# EDA-Robot_V1_2.net
KiCad netlist of a schematic drawn in EasyEDA Pro
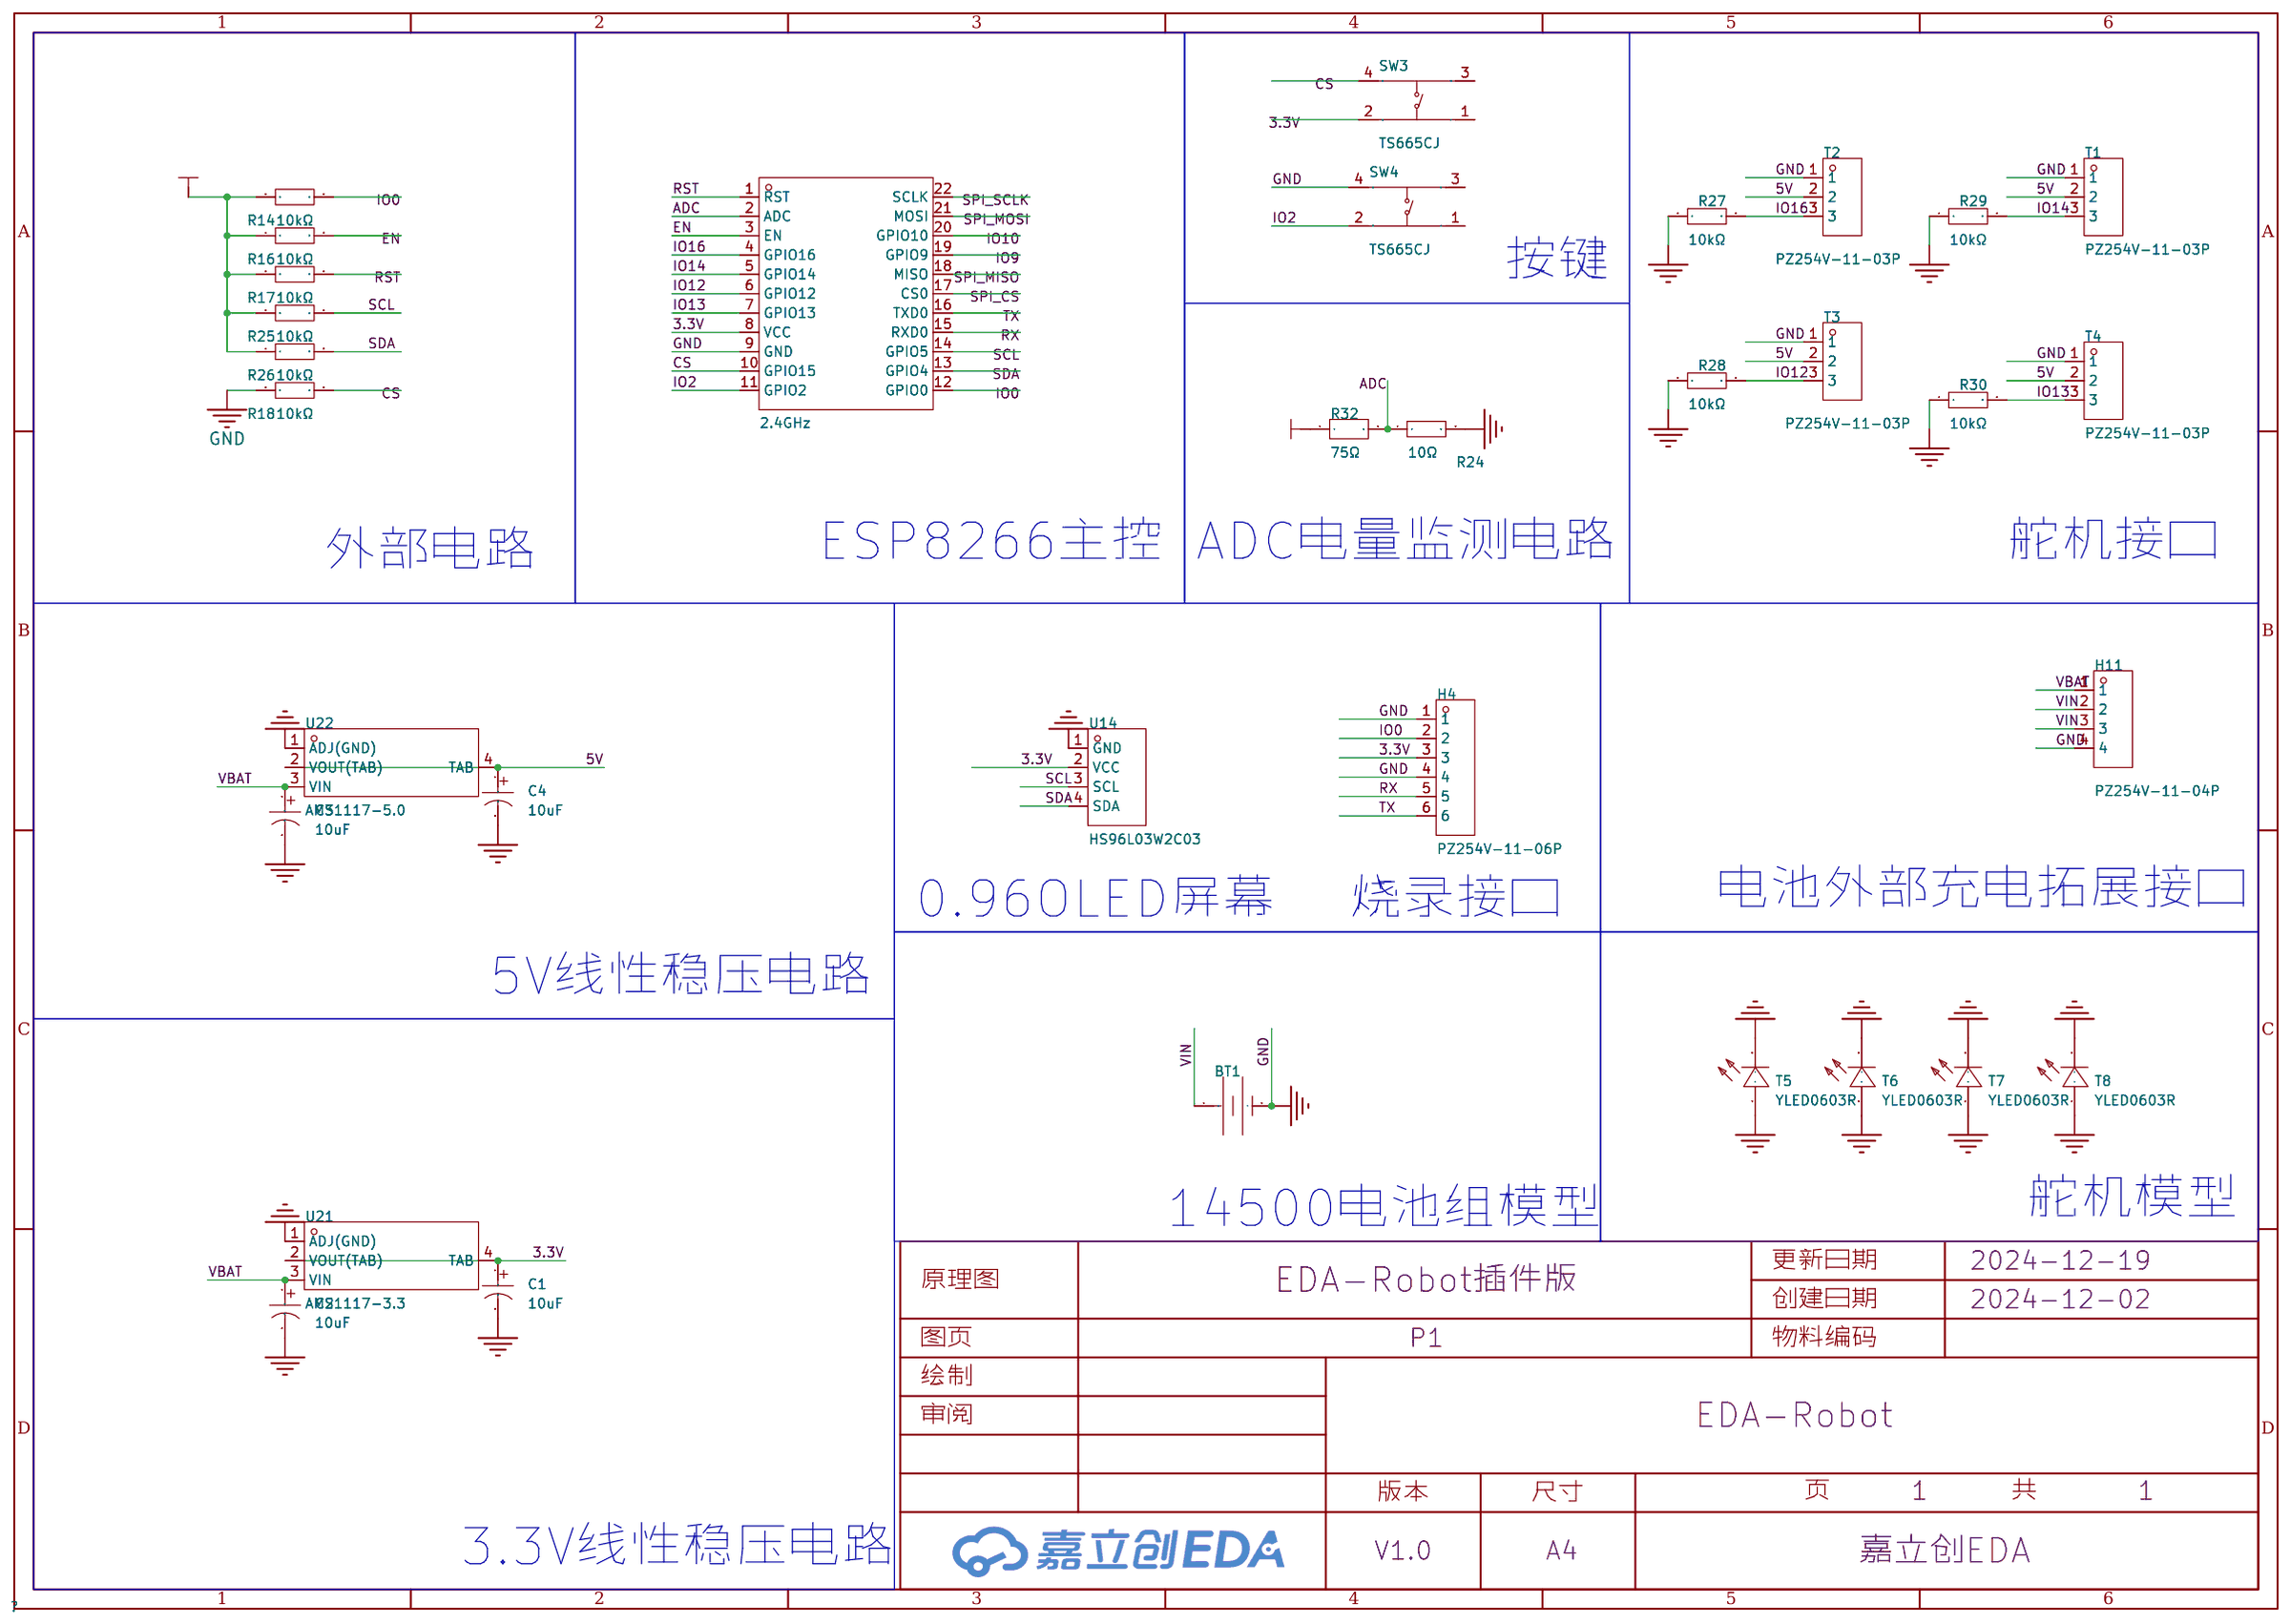
[diagram p0: schematic sheet]

(export (version "E")
  (design (tool "Eeschema 10.0.6"))
  (components
    (comp (ref "BT1")
      (value "BS-12-B3AA003")
      (footprint "easyedapro:BAT-SMD_BS-12-B3AA011")
      (description "连接器类型:电池底座;适用电池规格:CR1220;触头材质:磷青铜;工作温度范围:-25°C~+85°C;")
      (fields (field (name "Manufacturer") "MYOUNG(美阳)"))
      (libsource (lib "easyedapro") (part "BS-12-B3AA003"))
    )
    (comp (ref "C1")
      (value "10uF")
      (footprint "easyedapro:CAP-TH_BD4.0-P1.50-D0.8-FD")
      (description "容值:10uF;精度:±20%;额定电压:25V;纹波电流:29mA@120Hz;等效串联电阻:-;")
      (fields
        (field (name "Manufacturer Part") "KS106M025C07RR0VH2FP0")
        (field (name "Manufacturer") "CX(承兴)")
      )
      (libsource (lib "easyedapro") (part "10uF 25V 4*7"))
    )
    (comp (ref "C2")
      (value "10uF")
      (footprint "easyedapro:CAP-TH_BD4.0-P1.50-D0.8-FD")
      (description "容值:10uF;精度:±20%;额定电压:25V;纹波电流:29mA@120Hz;等效串联电阻:-;")
      (fields
        (field (name "Manufacturer Part") "KS106M025C07RR0VH2FP0")
        (field (name "Manufacturer") "CX(承兴)")
      )
      (libsource (lib "easyedapro") (part "10uF 25V 4*7"))
    )
    (comp (ref "C3")
      (value "10uF")
      (footprint "easyedapro:CAP-TH_BD4.0-P1.50-D0.8-FD")
      (description "容值:10uF;精度:±20%;额定电压:25V;纹波电流:29mA@120Hz;等效串联电阻:-;")
      (fields
        (field (name "Manufacturer Part") "KS106M025C07RR0VH2FP0")
        (field (name "Manufacturer") "CX(承兴)")
      )
      (libsource (lib "easyedapro") (part "10uF 25V 4*7"))
    )
    (comp (ref "C4")
      (value "10uF")
      (footprint "easyedapro:CAP-TH_BD4.0-P1.50-D0.8-FD")
      (description "容值:10uF;精度:±20%;额定电压:25V;纹波电流:29mA@120Hz;等效串联电阻:-;")
      (fields
        (field (name "Manufacturer Part") "KS106M025C07RR0VH2FP0")
        (field (name "Manufacturer") "CX(承兴)")
      )
      (libsource (lib "easyedapro") (part "10uF 25V 4*7"))
    )
    (comp (ref "H4")
      (value "PZ254V-11-06P")
      (footprint "easyedapro:HDR-TH_6P-P2.54-V-M")
      (fields (field (name "Manufacturer") "XFCN(兴飞)"))
      (libsource (lib "easyedapro") (part "PZ254V-11-06P"))
    )
    (comp (ref "H11")
      (value "PZ254V-11-04P")
      (footprint "easyedapro:HDR-TH_4P-P2.54-V-M")
      (fields (field (name "Manufacturer") "XFCN(兴飞)"))
      (libsource (lib "easyedapro") (part "PZ254V-11-04P_C2691448"))
    )
    (comp (ref "R14")
      (value "10kΩ")
      (footprint "easyedapro:R0805")
      (description "电阻类型:厚膜电阻;阻值:10kΩ;精度:±5%;功率:125mW;最大工作电压:150V;温度系数:±100ppm/°C;")
      (fields
        (field (name "Manufacturer Part") "RN1/4W10KFT/BA1")
        (field (name "Manufacturer") "Tyohm(幸亚电阻)")
      )
      (libsource (lib "easyedapro") (part "0805W8J0103T5E"))
    )
    (comp (ref "R16")
      (value "10kΩ")
      (footprint "easyedapro:R0805")
      (description "电阻类型:厚膜电阻;阻值:10kΩ;精度:±5%;功率:125mW;最大工作电压:150V;温度系数:±100ppm/°C;")
      (fields
        (field (name "Manufacturer Part") "RN1/4W10KFT/BA1")
        (field (name "Manufacturer") "Tyohm(幸亚电阻)")
      )
      (libsource (lib "easyedapro") (part "0805W8J0103T5E"))
    )
    (comp (ref "R17")
      (value "10kΩ")
      (footprint "easyedapro:R0805")
      (description "电阻类型:厚膜电阻;阻值:10kΩ;精度:±5%;功率:125mW;最大工作电压:150V;温度系数:±100ppm/°C;")
      (fields
        (field (name "Manufacturer Part") "RN1/4W10KFT/BA1")
        (field (name "Manufacturer") "Tyohm(幸亚电阻)")
      )
      (libsource (lib "easyedapro") (part "0805W8J0103T5E"))
    )
    (comp (ref "R18")
      (value "10kΩ")
      (footprint "easyedapro:R0805")
      (description "电阻类型:厚膜电阻;阻值:10kΩ;精度:±5%;功率:125mW;最大工作电压:150V;温度系数:±100ppm/°C;")
      (fields
        (field (name "Manufacturer Part") "RN1/4W10KFT/BA1")
        (field (name "Manufacturer") "Tyohm(幸亚电阻)")
      )
      (libsource (lib "easyedapro") (part "0805W8J0103T5E"))
    )
    (comp (ref "R24")
      (value "10Ω")
      (footprint "easyedapro:R0805")
      (description "电阻类型:厚膜电阻;阻值:10kΩ;精度:±5%;功率:125mW;最大工作电压:150V;温度系数:±100ppm/°C;")
      (fields (field (name "Manufacturer Part") "MFR-25FTE52-10R") (field (name "Manufacturer") "YAGEO(国巨)"))
      (libsource (lib "easyedapro") (part "0805W8J0103T5E"))
    )
    (comp (ref "R25")
      (value "10kΩ")
      (footprint "easyedapro:R0805")
      (description "电阻类型:厚膜电阻;阻值:10kΩ;精度:±5%;功率:125mW;最大工作电压:150V;温度系数:±100ppm/°C;")
      (fields
        (field (name "Manufacturer Part") "RN1/4W10KFT/BA1")
        (field (name "Manufacturer") "Tyohm(幸亚电阻)")
      )
      (libsource (lib "easyedapro") (part "0805W8J0103T5E"))
    )
    (comp (ref "R26")
      (value "10kΩ")
      (footprint "easyedapro:R0805")
      (description "电阻类型:厚膜电阻;阻值:10kΩ;精度:±5%;功率:125mW;最大工作电压:150V;温度系数:±100ppm/°C;")
      (fields
        (field (name "Manufacturer Part") "RN1/4W10KFT/BA1")
        (field (name "Manufacturer") "Tyohm(幸亚电阻)")
      )
      (libsource (lib "easyedapro") (part "0805W8J0103T5E"))
    )
    (comp (ref "R27")
      (value "10kΩ")
      (footprint "easyedapro:R0805")
      (description "电阻类型:厚膜电阻;阻值:10kΩ;精度:±5%;功率:125mW;最大工作电压:150V;温度系数:±100ppm/°C;")
      (fields
        (field (name "Manufacturer Part") "RN1/4W10KFT/BA1")
        (field (name "Manufacturer") "Tyohm(幸亚电阻)")
      )
      (libsource (lib "easyedapro") (part "0805W8J0103T5E"))
    )
    (comp (ref "R28")
      (value "10kΩ")
      (footprint "easyedapro:R0805")
      (description "电阻类型:厚膜电阻;阻值:10kΩ;精度:±5%;功率:125mW;最大工作电压:150V;温度系数:±100ppm/°C;")
      (fields
        (field (name "Manufacturer Part") "RN1/4W10KFT/BA1")
        (field (name "Manufacturer") "Tyohm(幸亚电阻)")
      )
      (libsource (lib "easyedapro") (part "0805W8J0103T5E"))
    )
    (comp (ref "R29")
      (value "10kΩ")
      (footprint "easyedapro:R0805")
      (description "电阻类型:厚膜电阻;阻值:10kΩ;精度:±5%;功率:125mW;最大工作电压:150V;温度系数:±100ppm/°C;")
      (fields
        (field (name "Manufacturer Part") "RN1/4W10KFT/BA1")
        (field (name "Manufacturer") "Tyohm(幸亚电阻)")
      )
      (libsource (lib "easyedapro") (part "0805W8J0103T5E"))
    )
    (comp (ref "R30")
      (value "10kΩ")
      (footprint "easyedapro:R0805")
      (description "电阻类型:厚膜电阻;阻值:10kΩ;精度:±5%;功率:125mW;最大工作电压:150V;温度系数:±100ppm/°C;")
      (fields
        (field (name "Manufacturer Part") "RN1/4W10KFT/BA1")
        (field (name "Manufacturer") "Tyohm(幸亚电阻)")
      )
      (libsource (lib "easyedapro") (part "0805W8J0103T5E"))
    )
    (comp (ref "R32")
      (value "75Ω")
      (footprint "easyedapro:RES-TH_BD2.4-L6.3-P10.30-D0.6")
      (description "电阻类型:金属膜电阻;阻值:75Ω;精度:±1%;功率:250mW;温度系数:±50ppm/°C;")
      (fields (field (name "Manufacturer Part") "MFR-25FTE52-75R") (field (name "Manufacturer") "YAGEO(国巨)"))
      (libsource (lib "easyedapro") (part "MFR-25FTE52-75R"))
    )
    (comp (ref "SW3")
      (value "TS665CJ")
      (footprint "easyedapro:SW-TH_4P-L6.0-W6.0-P4.50-LS6.5")
      (description "电路结构:单刀单掷;按钮形状:圆形按钮;安装方式:直插;开关长度:6mm;开关宽度:6mm;开关高度:5mm;触点电流:50mA;额定电压(DC):12V;带灯:-;机械寿命:-;")
      (fields (field (name "Manufacturer") "SHOU HAN(首韩)"))
      (libsource (lib "easyedapro") (part "TS665CJ"))
    )
    (comp (ref "SW4")
      (value "TS665CJ")
      (footprint "easyedapro:SW-TH_4P-L6.0-W6.0-P4.50-LS6.5")
      (description "电路结构:单刀单掷;按钮形状:圆形按钮;安装方式:直插;开关长度:6mm;开关宽度:6mm;开关高度:5mm;触点电流:50mA;额定电压(DC):12V;带灯:-;机械寿命:-;")
      (fields (field (name "Manufacturer") "SHOU HAN(首韩)"))
      (libsource (lib "easyedapro") (part "TS665CJ"))
    )
    (comp (ref "T1")
      (value "PZ254V-11-03P")
      (footprint "easyedapro:HDR-TH_3P-P2.54-V-M")
      (fields (field (name "Manufacturer") "XFCN(兴飞)"))
      (libsource (lib "easyedapro") (part "PZ254V-11-03P_C2937625"))
    )
    (comp (ref "T2")
      (value "PZ254V-11-03P")
      (footprint "easyedapro:HDR-TH_3P-P2.54-V-M")
      (fields (field (name "Manufacturer") "XFCN(兴飞)"))
      (libsource (lib "easyedapro") (part "PZ254V-11-03P_C2937625"))
    )
    (comp (ref "T3")
      (value "PZ254V-11-03P")
      (footprint "easyedapro:HDR-TH_3P-P2.54-V-M")
      (fields (field (name "Manufacturer") "XFCN(兴飞)"))
      (libsource (lib "easyedapro") (part "PZ254V-11-03P_C2937625"))
    )
    (comp (ref "T4")
      (value "PZ254V-11-03P")
      (footprint "easyedapro:HDR-TH_3P-P2.54-V-M")
      (fields (field (name "Manufacturer") "XFCN(兴飞)"))
      (libsource (lib "easyedapro") (part "PZ254V-11-03P_C2937625"))
    )
    (comp (ref "T5")
      (value "YLED0603R")
      (footprint "easyedapro:LED0603-FD")
      (fields (field (name "Manufacturer") "YONGYUTAI(永裕泰)"))
      (libsource (lib "easyedapro") (part "YLED0603R"))
    )
    (comp (ref "T6")
      (value "YLED0603R")
      (footprint "easyedapro:LED0603-FD")
      (fields (field (name "Manufacturer") "YONGYUTAI(永裕泰)"))
      (libsource (lib "easyedapro") (part "YLED0603R"))
    )
    (comp (ref "T7")
      (value "YLED0603R")
      (footprint "easyedapro:LED0603-FD")
      (fields (field (name "Manufacturer") "YONGYUTAI(永裕泰)"))
      (libsource (lib "easyedapro") (part "YLED0603R"))
    )
    (comp (ref "T8")
      (value "YLED0603R")
      (footprint "easyedapro:LED0603-FD")
      (fields (field (name "Manufacturer") "YONGYUTAI(永裕泰)"))
      (libsource (lib "easyedapro") (part "YLED0603R"))
    )
    (comp (ref "U10")
      (value "2.4GHz")
      (footprint "easyedapro:WIFIM-SMD_ESP-12F-ESP8266MOD")
      (description "频率:2.4GHz;发射功率:16dBm;核心处理器:ESP8266;天线形式:PCB 板载天线;接收灵敏度:-90dBm;")
      (fields
        (field (name "Manufacturer Part") "ESP-12F(ESP8266MOD)")
        (field (name "Manufacturer") "Ai-Thinker(安信可)")
      )
      (libsource (lib "easyedapro") (part "ESP-12F(ESP8266MOD)"))
    )
    (comp (ref "U14")
      (value "HS96L03W2C03")
      (footprint "easyedapro:OLED-TH_L27.8-W27.2-P2.54_C9900033791")
      (description "主控芯片:SSD1315;接口类型:I2C;尺寸(inch):0.96;像素分辨率:128x64;")
      (fields (field (name "Manufacturer") "HS(汉昇)"))
      (libsource (lib "easyedapro") (part "HS96L03W2C03"))
    )
    (comp (ref "U21")
      (value "AMS1117-3.3")
      (footprint "easyedapro:SOT-223-4_L6.5-W3.5-P2.30-LS7.0-BR")
      (description "输出类型:固定;最大输入电压:18V;输出电压:3.3V;输出电流:1A;电源纹波抑制比(PSRR):60dB@(120Hz);输出极性:正极;")
      (fields (field (name "Manufacturer") "UMW(友台半导体)"))
      (libsource (lib "easyedapro") (part "AMS1117-3.3_C347222"))
    )
    (comp (ref "U22")
      (value "AMS1117-5.0")
      (footprint "easyedapro:SOT-223_L6.7-W3.5-P2.30-BR")
      (description "输出类型:固定;最大输入电压:12V;输出电压:5V;最大输出电流:1A;电源纹波抑制比(PSRR):60dB@(120Hz);输出极性:正极;")
      (fields (field (name "Manufacturer") "UMW(友台半导体)"))
      (libsource (lib "easyedapro") (part "AMS1117-5.0_C347223"))
    )
  )
  (nets
    (net (code "1") (name "/5V") (class "Default")
      (node (ref "C4") (pin "1") (pinfunction "1_1") (pintype "input"))
      (node (ref "T1") (pin "2") (pinfunction "2_2") (pintype "unspecified"))
      (node (ref "T2") (pin "2") (pinfunction "2_2") (pintype "unspecified"))
      (node (ref "T3") (pin "2") (pinfunction "2_2") (pintype "unspecified"))
      (node (ref "T4") (pin "2") (pinfunction "2_2") (pintype "unspecified"))
      (node (ref "U22") (pin "2") (pinfunction "VOUT(TAB)_2") (pintype "unspecified"))
      (node (ref "U22") (pin "4") (pinfunction "TAB_4") (pintype "unspecified"))
    )
    (net (code "2") (name "/ADC") (class "Default")
      (node (ref "R24") (pin "1") (pinfunction "1_1") (pintype "input"))
      (node (ref "R32") (pin "2") (pinfunction "2_2") (pintype "unspecified"))
      (node (ref "U10") (pin "2") (pinfunction "ADC_2") (pintype "input"))
    )
    (net (code "3") (name "/CS") (class "Default")
      (node (ref "R18") (pin "2") (pinfunction "2_2") (pintype "input"))
      (node (ref "SW3") (pin "4") (pinfunction "D_4") (pintype "unspecified"))
      (node (ref "U10") (pin "10") (pinfunction "GPIO15_10") (pintype "input"))
    )
    (net (code "4") (name "/EN") (class "Default")
      (node (ref "R16") (pin "2") (pinfunction "2_2") (pintype "input"))
      (node (ref "U10") (pin "3") (pinfunction "EN_3") (pintype "input"))
    )
    (net (code "5") (name "/IO0") (class "Default")
      (node (ref "H4") (pin "2") (pinfunction "2_2") (pintype "unspecified"))
      (node (ref "R14") (pin "2") (pinfunction "2_2") (pintype "input"))
      (node (ref "U10") (pin "12") (pinfunction "GPIO0_12") (pintype "input"))
    )
    (net (code "6") (name "/IO2") (class "Default")
      (node (ref "SW4") (pin "2") (pinfunction "B_2") (pintype "unspecified"))
      (node (ref "U10") (pin "11") (pinfunction "GPIO2_11") (pintype "input"))
    )
    (net (code "7") (name "/IO9") (class "Default")
      (node (ref "U10") (pin "19") (pinfunction "GPIO9_19") (pintype "input"))
    )
    (net (code "8") (name "/IO10") (class "Default")
      (node (ref "U10") (pin "20") (pinfunction "GPIO10_20") (pintype "input"))
    )
    (net (code "9") (name "/IO12") (class "Default")
      (node (ref "R28") (pin "2") (pinfunction "2_2") (pintype "input"))
      (node (ref "T3") (pin "3") (pinfunction "3_3") (pintype "unspecified"))
      (node (ref "U10") (pin "6") (pinfunction "GPIO12_6") (pintype "input"))
    )
    (net (code "10") (name "/IO13") (class "Default")
      (node (ref "R30") (pin "2") (pinfunction "2_2") (pintype "input"))
      (node (ref "T4") (pin "3") (pinfunction "3_3") (pintype "unspecified"))
      (node (ref "U10") (pin "7") (pinfunction "GPIO13_7") (pintype "input"))
    )
    (net (code "11") (name "/IO14") (class "Default")
      (node (ref "R29") (pin "2") (pinfunction "2_2") (pintype "input"))
      (node (ref "T1") (pin "3") (pinfunction "3_3") (pintype "unspecified"))
      (node (ref "U10") (pin "5") (pinfunction "GPIO14_5") (pintype "input"))
    )
    (net (code "12") (name "/IO16") (class "Default")
      (node (ref "R27") (pin "2") (pinfunction "2_2") (pintype "input"))
      (node (ref "T2") (pin "3") (pinfunction "3_3") (pintype "unspecified"))
      (node (ref "U10") (pin "4") (pinfunction "GPIO16_4") (pintype "input"))
    )
    (net (code "13") (name "/RST") (class "Default")
      (node (ref "R17") (pin "2") (pinfunction "2_2") (pintype "input"))
      (node (ref "U10") (pin "1") (pinfunction "RST_1") (pintype "input"))
    )
    (net (code "14") (name "/RX") (class "Default")
      (node (ref "H4") (pin "5") (pinfunction "5_5") (pintype "unspecified"))
      (node (ref "U10") (pin "15") (pinfunction "RXD0_15") (pintype "input"))
    )
    (net (code "15") (name "/SCL") (class "Default")
      (node (ref "R25") (pin "2") (pinfunction "2_2") (pintype "input"))
      (node (ref "U10") (pin "14") (pinfunction "GPIO5_14") (pintype "input"))
      (node (ref "U14") (pin "3") (pinfunction "SCL_3") (pintype "unspecified"))
    )
    (net (code "16") (name "/SDA") (class "Default")
      (node (ref "R26") (pin "2") (pinfunction "2_2") (pintype "input"))
      (node (ref "U10") (pin "13") (pinfunction "GPIO4_13") (pintype "input"))
      (node (ref "U14") (pin "4") (pinfunction "SDA_4") (pintype "unspecified"))
    )
    (net (code "17") (name "/SPI_CS") (class "Default")
      (node (ref "U10") (pin "17") (pinfunction "CS0_17") (pintype "input"))
    )
    (net (code "18") (name "/SPI_MISO") (class "Default")
      (node (ref "U10") (pin "18") (pinfunction "MISO_18") (pintype "input"))
    )
    (net (code "19") (name "/SPI_MOSI") (class "Default")
      (node (ref "U10") (pin "21") (pinfunction "MOSI_21") (pintype "input"))
    )
    (net (code "20") (name "/SPI_SCLK") (class "Default")
      (node (ref "U10") (pin "22") (pinfunction "SCLK_22") (pintype "input"))
    )
    (net (code "21") (name "/TX") (class "Default")
      (node (ref "H4") (pin "6") (pinfunction "6_6") (pintype "unspecified"))
      (node (ref "U10") (pin "16") (pinfunction "TXD0_16") (pintype "input"))
    )
    (net (code "22") (name "/VIN") (class "Default")
      (node (ref "BT1") (pin "1") (pinfunction "+_1") (pintype "unspecified"))
      (node (ref "H11") (pin "2") (pinfunction "2_2") (pintype "unspecified"))
      (node (ref "H11") (pin "3") (pinfunction "3_3") (pintype "unspecified"))
    )
    (net (code "23") (name "3.3V") (class "Default")
      (node (ref "C1") (pin "1") (pinfunction "1_1") (pintype "input"))
      (node (ref "H4") (pin "3") (pinfunction "3_3") (pintype "unspecified"))
      (node (ref "R14") (pin "1") (pinfunction "1_1") (pintype "input"))
      (node (ref "R16") (pin "1") (pinfunction "1_1") (pintype "input"))
      (node (ref "R17") (pin "1") (pinfunction "1_1") (pintype "input"))
      (node (ref "R25") (pin "1") (pinfunction "1_1") (pintype "input"))
      (node (ref "R26") (pin "1") (pinfunction "1_1") (pintype "input"))
      (node (ref "SW3") (pin "2") (pinfunction "B_2") (pintype "unspecified"))
      (node (ref "U10") (pin "8") (pinfunction "VCC_8") (pintype "input"))
      (node (ref "U14") (pin "2") (pinfunction "VCC_2") (pintype "unspecified"))
      (node (ref "U21") (pin "2") (pinfunction "VOUT(TAB)_2") (pintype "unspecified"))
      (node (ref "U21") (pin "4") (pinfunction "TAB_4") (pintype "unspecified"))
    )
    (net (code "24") (name "GND") (class "Default")
      (node (ref "BT1") (pin "2") (pinfunction "-_2") (pintype "unspecified"))
      (node (ref "C1") (pin "2") (pinfunction "2_2") (pintype "input"))
      (node (ref "C2") (pin "2") (pinfunction "2_2") (pintype "input"))
      (node (ref "C3") (pin "2") (pinfunction "2_2") (pintype "input"))
      (node (ref "C4") (pin "2") (pinfunction "2_2") (pintype "input"))
      (node (ref "H11") (pin "4") (pinfunction "4_4") (pintype "unspecified"))
      (node (ref "H4") (pin "1") (pinfunction "1_1") (pintype "unspecified"))
      (node (ref "H4") (pin "4") (pinfunction "4_4") (pintype "unspecified"))
      (node (ref "R18") (pin "1") (pinfunction "1_1") (pintype "input"))
      (node (ref "R24") (pin "2") (pinfunction "2_2") (pintype "input"))
      (node (ref "R27") (pin "1") (pinfunction "1_1") (pintype "input"))
      (node (ref "R28") (pin "1") (pinfunction "1_1") (pintype "input"))
      (node (ref "R29") (pin "1") (pinfunction "1_1") (pintype "input"))
      (node (ref "R30") (pin "1") (pinfunction "1_1") (pintype "input"))
      (node (ref "SW4") (pin "4") (pinfunction "D_4") (pintype "unspecified"))
      (node (ref "T1") (pin "1") (pinfunction "1_1") (pintype "unspecified"))
      (node (ref "T2") (pin "1") (pinfunction "1_1") (pintype "unspecified"))
      (node (ref "T3") (pin "1") (pinfunction "1_1") (pintype "unspecified"))
      (node (ref "T4") (pin "1") (pinfunction "1_1") (pintype "unspecified"))
      (node (ref "T5") (pin "1") (pinfunction "+_1") (pintype "unspecified"))
      (node (ref "T5") (pin "2") (pinfunction "-_2") (pintype "unspecified"))
      (node (ref "T6") (pin "1") (pinfunction "+_1") (pintype "unspecified"))
      (node (ref "T6") (pin "2") (pinfunction "-_2") (pintype "unspecified"))
      (node (ref "T7") (pin "1") (pinfunction "+_1") (pintype "unspecified"))
      (node (ref "T7") (pin "2") (pinfunction "-_2") (pintype "unspecified"))
      (node (ref "T8") (pin "1") (pinfunction "+_1") (pintype "unspecified"))
      (node (ref "T8") (pin "2") (pinfunction "-_2") (pintype "unspecified"))
      (node (ref "U10") (pin "9") (pinfunction "GND_9") (pintype "input"))
      (node (ref "U14") (pin "1") (pinfunction "GND_1") (pintype "unspecified"))
      (node (ref "U21") (pin "1") (pinfunction "ADJ(GND)_1") (pintype "unspecified"))
      (node (ref "U22") (pin "1") (pinfunction "ADJ(GND)_1") (pintype "unspecified"))
    )
    (net (code "25") (name "VBAT") (class "Default")
      (node (ref "C2") (pin "1") (pinfunction "1_1") (pintype "input"))
      (node (ref "C3") (pin "1") (pinfunction "1_1") (pintype "input"))
      (node (ref "H11") (pin "1") (pinfunction "1_1") (pintype "unspecified"))
      (node (ref "R32") (pin "1") (pinfunction "1_1") (pintype "unspecified"))
      (node (ref "U21") (pin "3") (pinfunction "VIN_3") (pintype "unspecified"))
      (node (ref "U22") (pin "3") (pinfunction "VIN_3") (pintype "unspecified"))
    )
    (net (code "26") (name "unconnected-(SW3-A-Pad1)") (class "Default")
      (node (ref "SW3") (pin "1") (pinfunction "A_1") (pintype "unspecified"))
    )
    (net (code "27") (name "unconnected-(SW3-C-Pad3)") (class "Default")
      (node (ref "SW3") (pin "3") (pinfunction "C_3") (pintype "unspecified"))
    )
    (net (code "28") (name "unconnected-(SW4-A-Pad1)") (class "Default")
      (node (ref "SW4") (pin "1") (pinfunction "A_1") (pintype "unspecified"))
    )
    (net (code "29") (name "unconnected-(SW4-C-Pad3)") (class "Default")
      (node (ref "SW4") (pin "3") (pinfunction "C_3") (pintype "unspecified"))
    )
  )
)
